# Voltage_Regulators.net
KiCad netlist of a schematic drawn in Altium Designer
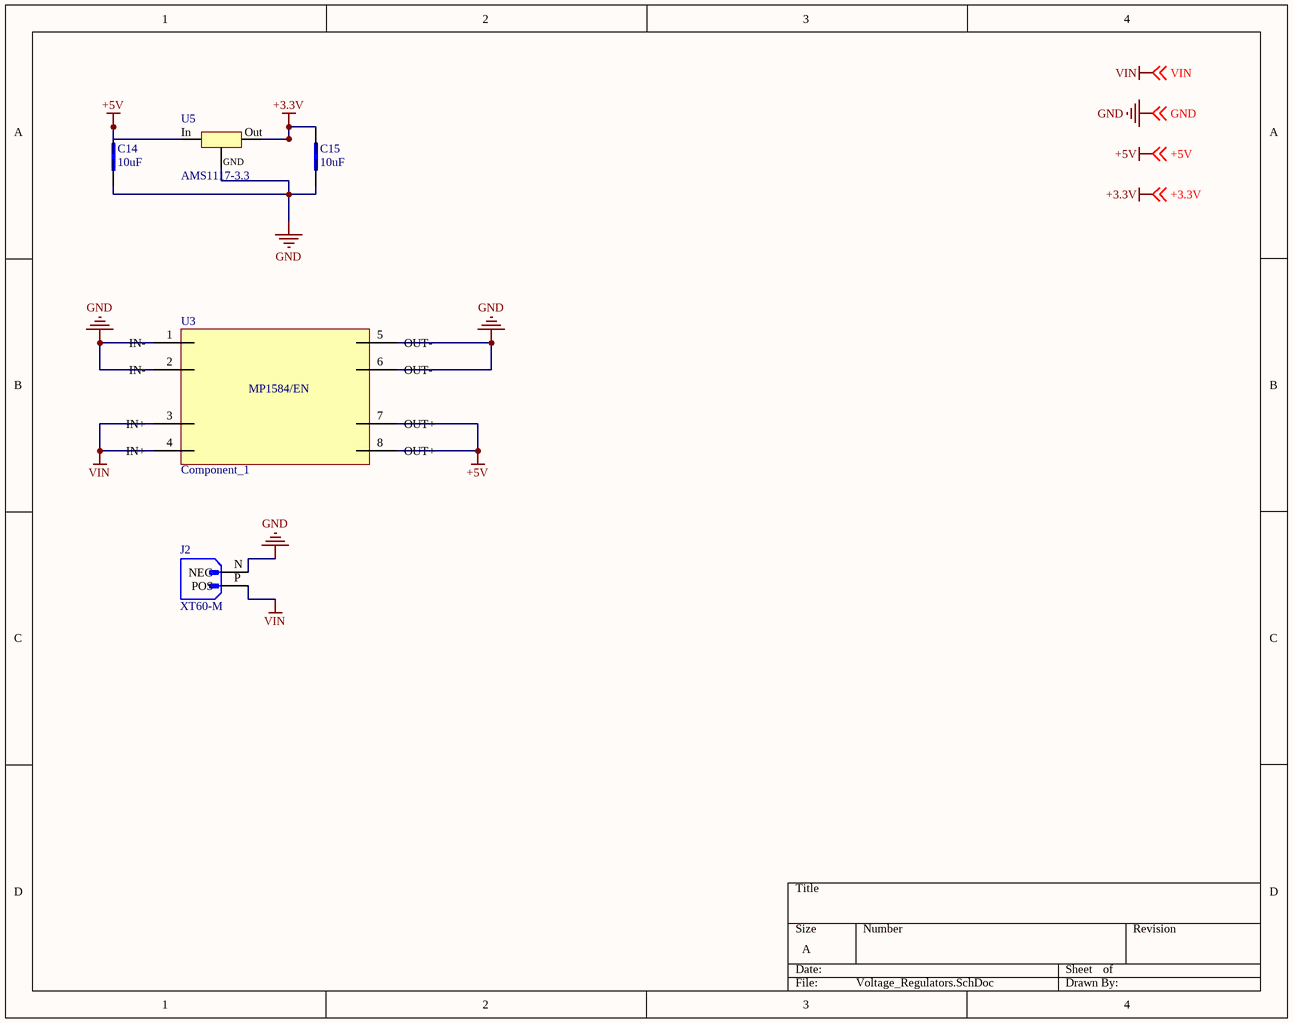
[diagram p0: Voltage_Regulators.SchDoc]

(export (version "E")
  (design (tool "Eeschema 10.0.6"))
  (components
    (comp (ref "C14")
      (value "10uF")
      (footprint "CAPC1608X90")
      (description "0.1ÂµF Â±10% 50V Ceramic Capacitor X7R 0603 (1608 Metric)")
      (fields (field (name "MP") "C0603C104K5RACTU") (field (name "DIGI-KEY_PART_NUMBER") "399-5089-1-ND"))
      (libsource (lib "C0603C104K5RACTU") (part "C0603C104K5RACTU"))
    )
    (comp (ref "C15")
      (value "10uF")
      (footprint "CAPC1608X90")
      (description "0.1ÂµF Â±10% 50V Ceramic Capacitor X7R 0603 (1608 Metric)")
      (fields (field (name "MP") "C0603C104K5RACTU") (field (name "DIGI-KEY_PART_NUMBER") "399-5089-1-ND"))
      (libsource (lib "C0603C104K5RACTU") (part "C0603C104K5RACTU"))
    )
    (comp (ref "J2")
      (value "XT60-M")
      (footprint "AMASS_XT60-M")
      (description "Plug; DC supply; XT60; male; PIN: 2; for cable; soldered; 30A; 500V")
      (fields (field (name "MF") "AMASS"))
      (libsource (lib "XT60-M") (part "XT60-M"))
    )
    (comp (ref "U3")
      (value "Component_1")
      (footprint "PCBComponent_1")
      (libsource (lib "BEC1") (part "Component_1"))
    )
    (comp (ref "U5")
      (value "AMS1117-3.3")
      (footprint "SOT223")
      (libsource (lib "jakobs_library") (part "AMS1117-3.3"))
    )
  )
  (nets
    (net (code "1") (name "+3.3V") (class "Default")
      (node (ref "C15") (pin "1") (pinfunction "1_1") (pintype "passive"))
      (node (ref "U5") (pin "2") (pinfunction "2_2") (pintype "passive"))
    )
    (net (code "2") (name "+5V") (class "Default")
      (node (ref "C14") (pin "1") (pinfunction "1_1") (pintype "passive"))
      (node (ref "U3") (pin "7") (pinfunction "OUT+_7") (pintype "passive"))
      (node (ref "U3") (pin "8") (pinfunction "OUT+_8") (pintype "passive"))
      (node (ref "U5") (pin "3") (pinfunction "3_3") (pintype "passive"))
    )
    (net (code "3") (name "GND") (class "Default")
      (node (ref "C14") (pin "2") (pinfunction "2_2") (pintype "passive"))
      (node (ref "C15") (pin "2") (pinfunction "2_2") (pintype "passive"))
      (node (ref "J2") (pin "N") (pinfunction "NEG_N") (pintype "passive"))
      (node (ref "U3") (pin "1") (pinfunction "IN-_1") (pintype "passive"))
      (node (ref "U3") (pin "2") (pinfunction "IN-_2") (pintype "passive"))
      (node (ref "U3") (pin "5") (pinfunction "OUT-_5") (pintype "passive"))
      (node (ref "U3") (pin "6") (pinfunction "OUT-_6") (pintype "passive"))
      (node (ref "U5") (pin "1") (pinfunction "1_1") (pintype "passive"))
    )
    (net (code "4") (name "VIN") (class "Default")
      (node (ref "J2") (pin "P") (pinfunction "POS_P") (pintype "passive"))
      (node (ref "U3") (pin "3") (pinfunction "IN+_3") (pintype "passive"))
      (node (ref "U3") (pin "4") (pinfunction "IN+_4") (pintype "passive"))
    )
  )
)
